# board_ports.net
KiCad netlist of a schematic drawn in Altium Designer
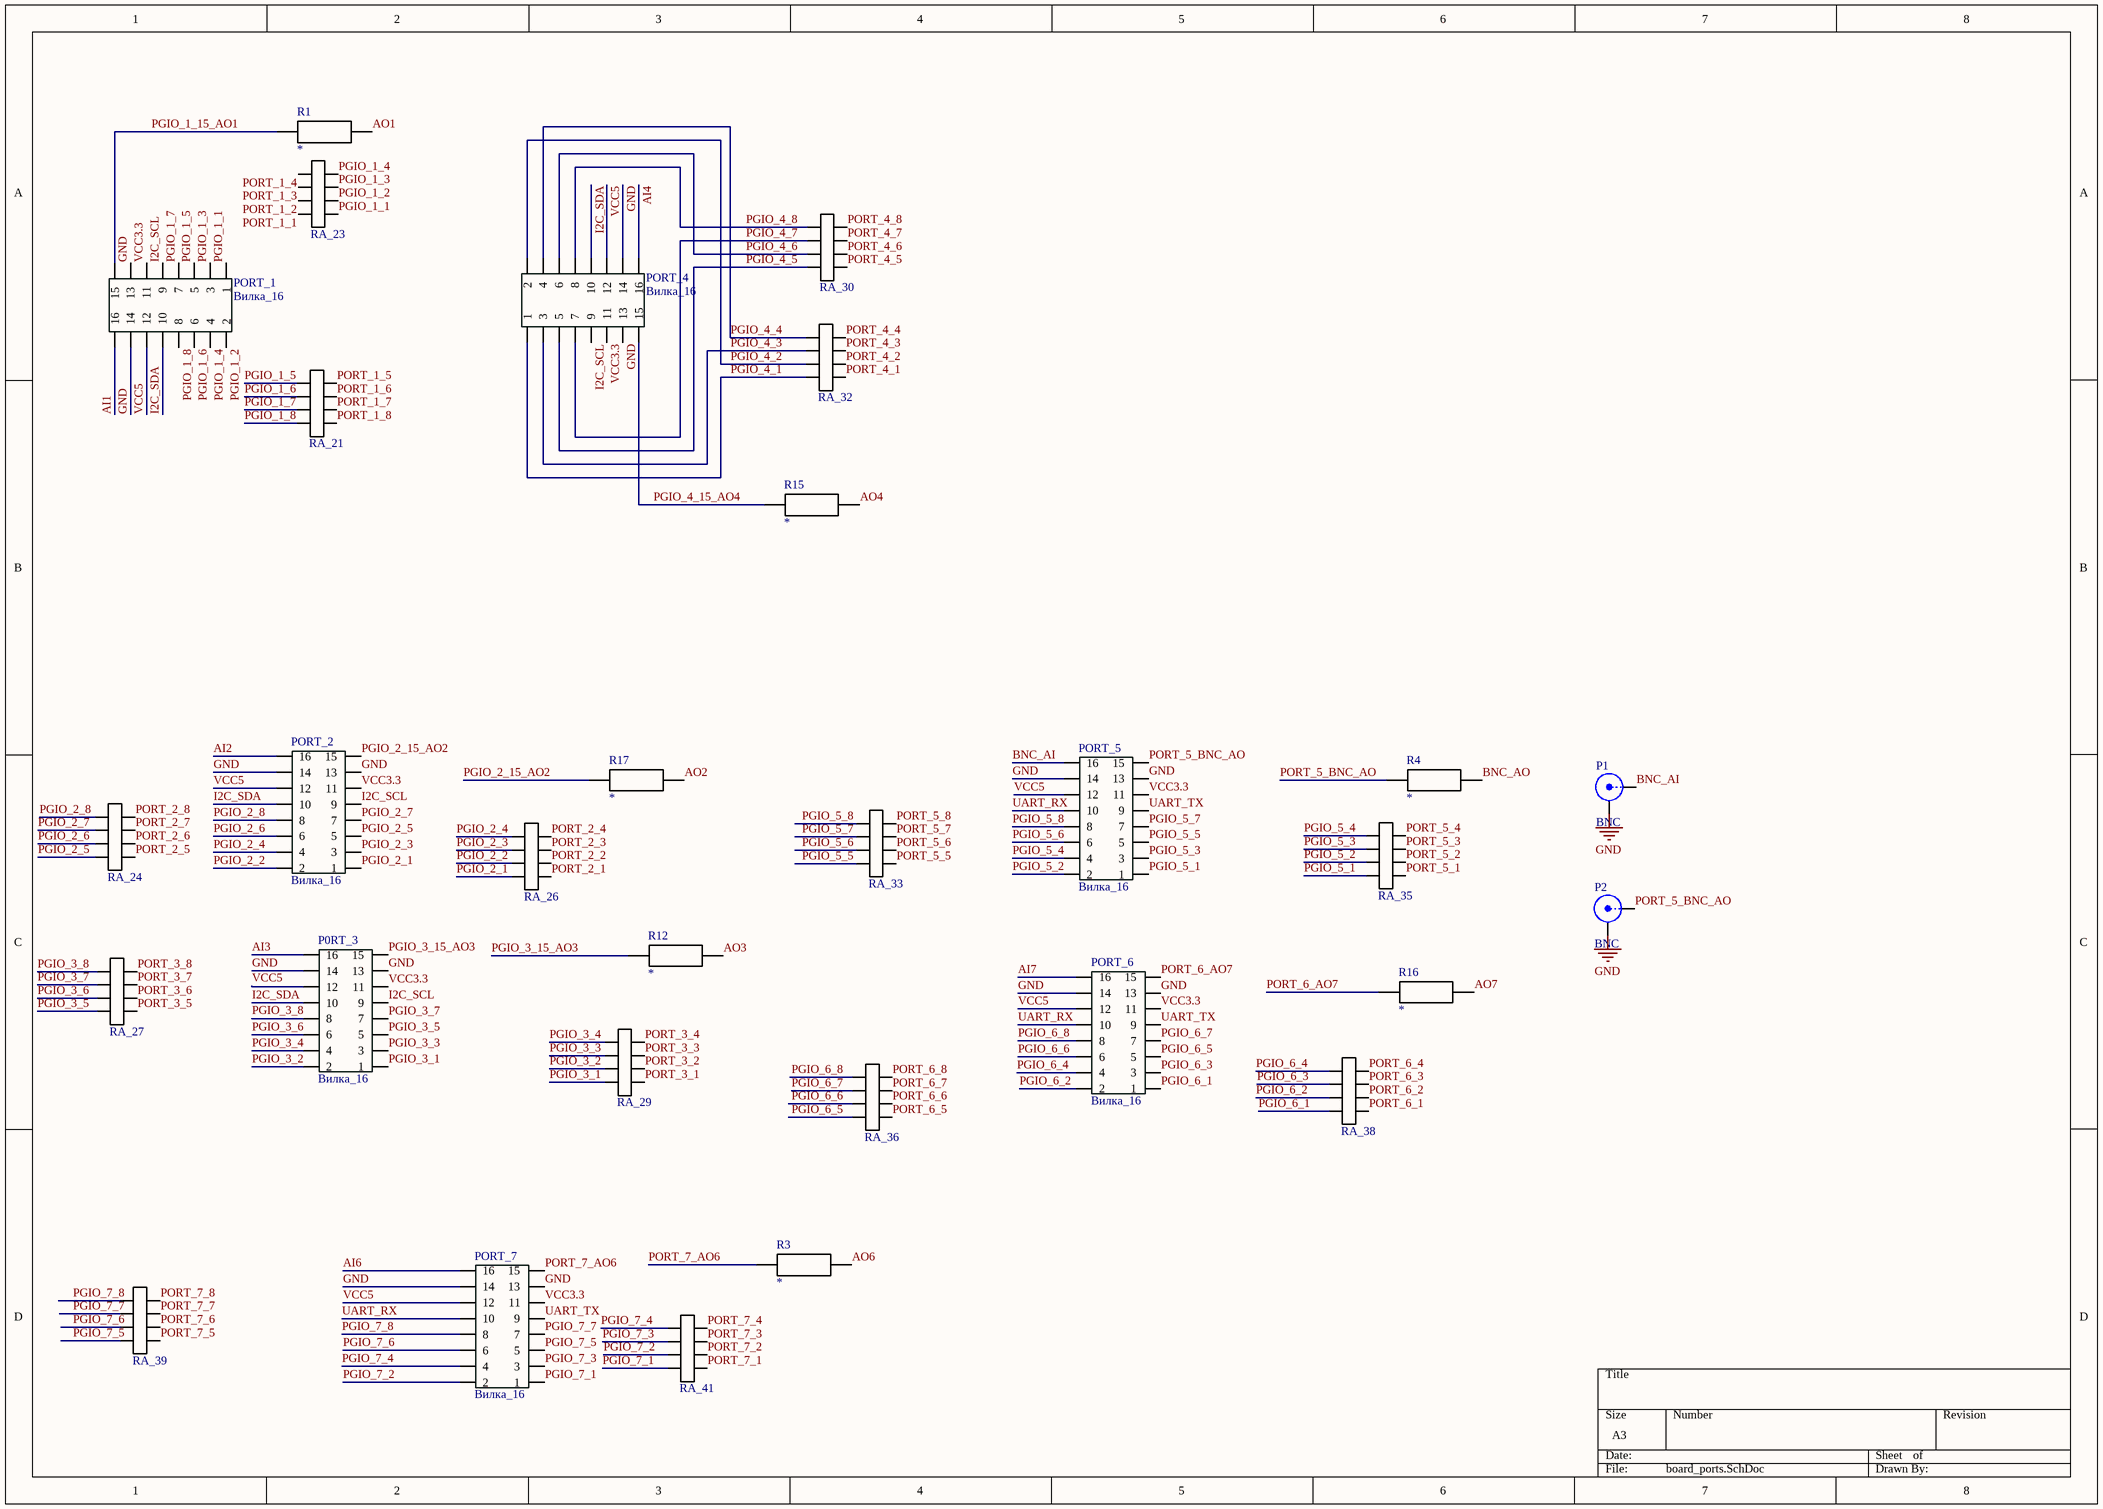
[diagram p0: board_ports.SchDoc]

(export (version "E")
  (design (tool "Eeschema 10.0.6"))
  (components
    (comp (ref "P0RT_3")
      (value "Вилка_16")
      (footprint "elvis_lib:DS1013-16")
      (description "16_pin")
      (libsource (lib "elvis_lib") (part "DS1013-16"))
    )
    (comp (ref "P1")
      (value "BNC")
      (footprint "BNC_RA CON")
      (description "BNC Elbow Connector")
      (fields (field (name "PUBLISHER") "Altium Limited"))
      (libsource (lib "Miscellaneous Connectors") (part "BNC"))
    )
    (comp (ref "P2")
      (value "BNC")
      (footprint "BNC_RA CON")
      (description "BNC Elbow Connector")
      (fields (field (name "PUBLISHER") "Altium Limited"))
      (libsource (lib "Miscellaneous Connectors") (part "BNC"))
    )
    (comp (ref "PORT_1")
      (value "Вилка_16")
      (footprint "elvis_lib:DS1013-16")
      (description "16_pin")
      (libsource (lib "elvis_lib") (part "DS1013-16"))
    )
    (comp (ref "PORT_2")
      (value "Вилка_16")
      (footprint "elvis_lib:DS1013-16")
      (description "16_pin")
      (libsource (lib "elvis_lib") (part "DS1013-16"))
    )
    (comp (ref "PORT_4")
      (value "Вилка_16")
      (footprint "elvis_lib:DS1013-16")
      (description "16_pin")
      (libsource (lib "elvis_lib") (part "DS1013-16"))
    )
    (comp (ref "PORT_5")
      (value "Вилка_16")
      (footprint "elvis_lib:DS1013-16")
      (description "16_pin")
      (libsource (lib "elvis_lib") (part "DS1013-16"))
    )
    (comp (ref "PORT_6")
      (value "Вилка_16")
      (footprint "elvis_lib:DS1013-16")
      (description "16_pin")
      (libsource (lib "elvis_lib") (part "DS1013-16"))
    )
    (comp (ref "PORT_7")
      (value "Вилка_16")
      (footprint "elvis_lib:DS1013-16")
      (description "16_pin")
      (libsource (lib "elvis_lib") (part "DS1013-16"))
    )
    (comp (ref "R1") (value "*") (footprint "elvis_lib:R0805") (libsource (lib "elvis_lib") (part "R0805")))
    (comp (ref "R3") (value "*") (footprint "elvis_lib:R0805") (libsource (lib "elvis_lib") (part "R0805")))
    (comp (ref "R4") (value "*") (footprint "elvis_lib:R0805") (libsource (lib "elvis_lib") (part "R0805")))
    (comp (ref "R12") (value "*") (footprint "elvis_lib:R0805") (libsource (lib "elvis_lib") (part "R0805")))
    (comp (ref "R15") (value "*") (footprint "elvis_lib:R0805") (libsource (lib "elvis_lib") (part "R0805")))
    (comp (ref "R16") (value "*") (footprint "elvis_lib:R0805") (libsource (lib "elvis_lib") (part "R0805")))
    (comp (ref "R17") (value "*") (footprint "elvis_lib:R0805") (libsource (lib "elvis_lib") (part "R0805")))
    (comp (ref "RA_21")
      (value "Bourns CAT16-102J4LF_1")
      (footprint "CAT16-102J4_NEW")
      (libsource (lib "elvis_lib") (part "Bourns CAT16-102J4LF_1"))
    )
    (comp (ref "RA_23")
      (value "Bourns CAT16-102J4LF_1")
      (footprint "CAT16-102J4_NEW")
      (libsource (lib "elvis_lib") (part "Bourns CAT16-102J4LF_1"))
    )
    (comp (ref "RA_24")
      (value "Bourns CAT16-102J4LF_1")
      (footprint "CAT16-102J4_NEW")
      (libsource (lib "elvis_lib") (part "Bourns CAT16-102J4LF_1"))
    )
    (comp (ref "RA_26")
      (value "Bourns CAT16-102J4LF_1")
      (footprint "CAT16-102J4_NEW")
      (libsource (lib "elvis_lib") (part "Bourns CAT16-102J4LF_1"))
    )
    (comp (ref "RA_27")
      (value "Bourns CAT16-102J4LF_1")
      (footprint "CAT16-102J4_NEW")
      (libsource (lib "elvis_lib") (part "Bourns CAT16-102J4LF_1"))
    )
    (comp (ref "RA_29")
      (value "Bourns CAT16-102J4LF_1")
      (footprint "CAT16-102J4_NEW")
      (libsource (lib "elvis_lib") (part "Bourns CAT16-102J4LF_1"))
    )
    (comp (ref "RA_30")
      (value "Bourns CAT16-102J4LF_1")
      (footprint "CAT16-102J4_NEW")
      (libsource (lib "elvis_lib") (part "Bourns CAT16-102J4LF_1"))
    )
    (comp (ref "RA_32")
      (value "Bourns CAT16-102J4LF_1")
      (footprint "CAT16-102J4_NEW")
      (libsource (lib "elvis_lib") (part "Bourns CAT16-102J4LF_1"))
    )
    (comp (ref "RA_33")
      (value "Bourns CAT16-102J4LF_1")
      (footprint "CAT16-102J4_NEW")
      (libsource (lib "elvis_lib") (part "Bourns CAT16-102J4LF_1"))
    )
    (comp (ref "RA_35")
      (value "Bourns CAT16-102J4LF_1")
      (footprint "CAT16-102J4_NEW")
      (libsource (lib "elvis_lib") (part "Bourns CAT16-102J4LF_1"))
    )
    (comp (ref "RA_36")
      (value "Bourns CAT16-102J4LF_1")
      (footprint "CAT16-102J4_NEW")
      (libsource (lib "elvis_lib") (part "Bourns CAT16-102J4LF_1"))
    )
    (comp (ref "RA_38")
      (value "Bourns CAT16-102J4LF_1")
      (footprint "CAT16-102J4_NEW")
      (libsource (lib "elvis_lib") (part "Bourns CAT16-102J4LF_1"))
    )
    (comp (ref "RA_39")
      (value "Bourns CAT16-102J4LF_1")
      (footprint "CAT16-102J4_NEW")
      (libsource (lib "elvis_lib") (part "Bourns CAT16-102J4LF_1"))
    )
    (comp (ref "RA_41")
      (value "Bourns CAT16-102J4LF_1")
      (footprint "CAT16-102J4_NEW")
      (libsource (lib "elvis_lib") (part "Bourns CAT16-102J4LF_1"))
    )
  )
  (nets
    (net (code "1") (name "/AI1") (class "Default")
      (node (ref "PORT_1") (pin "16") (pinfunction "16_16") (pintype "passive"))
    )
    (net (code "2") (name "/AI2") (class "Default")
      (node (ref "PORT_2") (pin "16") (pinfunction "16_16") (pintype "passive"))
    )
    (net (code "3") (name "/AI3") (class "Default")
      (node (ref "P0RT_3") (pin "16") (pinfunction "16_16") (pintype "passive"))
    )
    (net (code "4") (name "/AI4") (class "Default")
      (node (ref "PORT_4") (pin "16") (pinfunction "16_16") (pintype "passive"))
    )
    (net (code "5") (name "/AI6") (class "Default")
      (node (ref "PORT_7") (pin "16") (pinfunction "16_16") (pintype "passive"))
    )
    (net (code "6") (name "/AI7") (class "Default")
      (node (ref "PORT_6") (pin "16") (pinfunction "16_16") (pintype "passive"))
    )
    (net (code "7") (name "/AO1") (class "Default")
      (node (ref "R1") (pin "2") (pinfunction "2_2") (pintype "passive"))
    )
    (net (code "8") (name "/AO2") (class "Default")
      (node (ref "R17") (pin "2") (pinfunction "2_2") (pintype "passive"))
    )
    (net (code "9") (name "/AO3") (class "Default")
      (node (ref "R12") (pin "2") (pinfunction "2_2") (pintype "passive"))
    )
    (net (code "10") (name "/AO4") (class "Default")
      (node (ref "R15") (pin "2") (pinfunction "2_2") (pintype "passive"))
    )
    (net (code "11") (name "/AO6") (class "Default")
      (node (ref "R3") (pin "2") (pinfunction "2_2") (pintype "passive"))
    )
    (net (code "12") (name "/AO7") (class "Default")
      (node (ref "R16") (pin "2") (pinfunction "2_2") (pintype "passive"))
    )
    (net (code "13") (name "/BNC_AI") (class "Default")
      (node (ref "P1") (pin "1") (pinfunction "X_1") (pintype "passive"))
      (node (ref "PORT_5") (pin "16") (pinfunction "16_16") (pintype "passive"))
    )
    (net (code "14") (name "/BNC_AO") (class "Default")
      (node (ref "R4") (pin "2") (pinfunction "2_2") (pintype "passive"))
    )
    (net (code "15") (name "/I2C_SCL") (class "Default")
      (node (ref "P0RT_3") (pin "9") (pinfunction "9_9") (pintype "passive"))
      (node (ref "PORT_1") (pin "9") (pinfunction "9_9") (pintype "passive"))
      (node (ref "PORT_2") (pin "9") (pinfunction "9_9") (pintype "passive"))
      (node (ref "PORT_4") (pin "9") (pinfunction "9_9") (pintype "passive"))
    )
    (net (code "16") (name "/I2C_SDA") (class "Default")
      (node (ref "P0RT_3") (pin "10") (pinfunction "10_10") (pintype "passive"))
      (node (ref "PORT_1") (pin "10") (pinfunction "10_10") (pintype "passive"))
      (node (ref "PORT_2") (pin "10") (pinfunction "10_10") (pintype "passive"))
      (node (ref "PORT_4") (pin "10") (pinfunction "10_10") (pintype "passive"))
    )
    (net (code "17") (name "/PGIO_1_1") (class "Default")
      (node (ref "PORT_1") (pin "1") (pinfunction "1_1") (pintype "passive"))
      (node (ref "RA_23") (pin "7") (pinfunction "7_7") (pintype "passive"))
    )
    (net (code "18") (name "/PGIO_1_2") (class "Default")
      (node (ref "PORT_1") (pin "2") (pinfunction "2_2") (pintype "passive"))
      (node (ref "RA_23") (pin "6") (pinfunction "6_6") (pintype "passive"))
    )
    (net (code "19") (name "/PGIO_1_3") (class "Default")
      (node (ref "PORT_1") (pin "3") (pinfunction "3_3") (pintype "passive"))
      (node (ref "RA_23") (pin "5") (pinfunction "5_5") (pintype "passive"))
    )
    (net (code "20") (name "/PGIO_1_4") (class "Default")
      (node (ref "PORT_1") (pin "4") (pinfunction "4_4") (pintype "passive"))
      (node (ref "RA_23") (pin "4") (pinfunction "4_4") (pintype "passive"))
    )
    (net (code "21") (name "/PGIO_1_5") (class "Default")
      (node (ref "PORT_1") (pin "5") (pinfunction "5_5") (pintype "passive"))
      (node (ref "RA_21") (pin "3") (pinfunction "3_3") (pintype "passive"))
    )
    (net (code "22") (name "/PGIO_1_6") (class "Default")
      (node (ref "PORT_1") (pin "6") (pinfunction "6_6") (pintype "passive"))
      (node (ref "RA_21") (pin "2") (pinfunction "2_2") (pintype "passive"))
    )
    (net (code "23") (name "/PGIO_1_7") (class "Default")
      (node (ref "PORT_1") (pin "7") (pinfunction "7_7") (pintype "passive"))
      (node (ref "RA_21") (pin "1") (pinfunction "1_1") (pintype "passive"))
    )
    (net (code "24") (name "/PGIO_1_8") (class "Default")
      (node (ref "PORT_1") (pin "8") (pinfunction "8_8") (pintype "passive"))
      (node (ref "RA_21") (pin "0") (pinfunction "0_0") (pintype "passive"))
    )
    (net (code "25") (name "/PGIO_1_15_AO1") (class "Default")
      (node (ref "PORT_1") (pin "15") (pinfunction "15_15") (pintype "passive"))
      (node (ref "R1") (pin "1") (pinfunction "1_1") (pintype "passive"))
    )
    (net (code "26") (name "/PGIO_2_1") (class "Default")
      (node (ref "PORT_2") (pin "1") (pinfunction "1_1") (pintype "passive"))
      (node (ref "RA_26") (pin "4") (pinfunction "4_4") (pintype "passive"))
    )
    (net (code "27") (name "/PGIO_2_2") (class "Default")
      (node (ref "PORT_2") (pin "2") (pinfunction "2_2") (pintype "passive"))
      (node (ref "RA_26") (pin "5") (pinfunction "5_5") (pintype "passive"))
    )
    (net (code "28") (name "/PGIO_2_3") (class "Default")
      (node (ref "PORT_2") (pin "3") (pinfunction "3_3") (pintype "passive"))
      (node (ref "RA_26") (pin "6") (pinfunction "6_6") (pintype "passive"))
    )
    (net (code "29") (name "/PGIO_2_4") (class "Default")
      (node (ref "PORT_2") (pin "4") (pinfunction "4_4") (pintype "passive"))
      (node (ref "RA_26") (pin "7") (pinfunction "7_7") (pintype "passive"))
    )
    (net (code "30") (name "/PGIO_2_5") (class "Default")
      (node (ref "PORT_2") (pin "5") (pinfunction "5_5") (pintype "passive"))
      (node (ref "RA_24") (pin "0") (pinfunction "0_0") (pintype "passive"))
    )
    (net (code "31") (name "/PGIO_2_6") (class "Default")
      (node (ref "PORT_2") (pin "6") (pinfunction "6_6") (pintype "passive"))
      (node (ref "RA_24") (pin "1") (pinfunction "1_1") (pintype "passive"))
    )
    (net (code "32") (name "/PGIO_2_7") (class "Default")
      (node (ref "PORT_2") (pin "7") (pinfunction "7_7") (pintype "passive"))
      (node (ref "RA_24") (pin "2") (pinfunction "2_2") (pintype "passive"))
    )
    (net (code "33") (name "/PGIO_2_8") (class "Default")
      (node (ref "PORT_2") (pin "8") (pinfunction "8_8") (pintype "passive"))
      (node (ref "RA_24") (pin "3") (pinfunction "3_3") (pintype "passive"))
    )
    (net (code "34") (name "/PGIO_2_15_AO2") (class "Default")
      (node (ref "PORT_2") (pin "15") (pinfunction "15_15") (pintype "passive"))
      (node (ref "R17") (pin "1") (pinfunction "1_1") (pintype "passive"))
    )
    (net (code "35") (name "/PGIO_3_1") (class "Default")
      (node (ref "P0RT_3") (pin "1") (pinfunction "1_1") (pintype "passive"))
      (node (ref "RA_29") (pin "0") (pinfunction "0_0") (pintype "passive"))
    )
    (net (code "36") (name "/PGIO_3_2") (class "Default")
      (node (ref "P0RT_3") (pin "2") (pinfunction "2_2") (pintype "passive"))
      (node (ref "RA_29") (pin "1") (pinfunction "1_1") (pintype "passive"))
    )
    (net (code "37") (name "/PGIO_3_3") (class "Default")
      (node (ref "P0RT_3") (pin "3") (pinfunction "3_3") (pintype "passive"))
      (node (ref "RA_29") (pin "2") (pinfunction "2_2") (pintype "passive"))
    )
    (net (code "38") (name "/PGIO_3_4") (class "Default")
      (node (ref "P0RT_3") (pin "4") (pinfunction "4_4") (pintype "passive"))
      (node (ref "RA_29") (pin "3") (pinfunction "3_3") (pintype "passive"))
    )
    (net (code "39") (name "/PGIO_3_5") (class "Default")
      (node (ref "P0RT_3") (pin "5") (pinfunction "5_5") (pintype "passive"))
      (node (ref "RA_27") (pin "0") (pinfunction "0_0") (pintype "passive"))
    )
    (net (code "40") (name "/PGIO_3_6") (class "Default")
      (node (ref "P0RT_3") (pin "6") (pinfunction "6_6") (pintype "passive"))
      (node (ref "RA_27") (pin "1") (pinfunction "1_1") (pintype "passive"))
    )
    (net (code "41") (name "/PGIO_3_7") (class "Default")
      (node (ref "P0RT_3") (pin "7") (pinfunction "7_7") (pintype "passive"))
      (node (ref "RA_27") (pin "2") (pinfunction "2_2") (pintype "passive"))
    )
    (net (code "42") (name "/PGIO_3_8") (class "Default")
      (node (ref "P0RT_3") (pin "8") (pinfunction "8_8") (pintype "passive"))
      (node (ref "RA_27") (pin "3") (pinfunction "3_3") (pintype "passive"))
    )
    (net (code "43") (name "/PGIO_3_15_AO3") (class "Default")
      (node (ref "P0RT_3") (pin "15") (pinfunction "15_15") (pintype "passive"))
      (node (ref "R12") (pin "1") (pinfunction "1_1") (pintype "passive"))
    )
    (net (code "44") (name "/PGIO_4_1") (class "Default")
      (node (ref "PORT_4") (pin "1") (pinfunction "1_1") (pintype "passive"))
      (node (ref "RA_32") (pin "4") (pinfunction "4_4") (pintype "passive"))
    )
    (net (code "45") (name "/PGIO_4_2") (class "Default")
      (node (ref "PORT_4") (pin "2") (pinfunction "2_2") (pintype "passive"))
      (node (ref "RA_32") (pin "5") (pinfunction "5_5") (pintype "passive"))
    )
    (net (code "46") (name "/PGIO_4_3") (class "Default")
      (node (ref "PORT_4") (pin "3") (pinfunction "3_3") (pintype "passive"))
      (node (ref "RA_32") (pin "6") (pinfunction "6_6") (pintype "passive"))
    )
    (net (code "47") (name "/PGIO_4_4") (class "Default")
      (node (ref "PORT_4") (pin "4") (pinfunction "4_4") (pintype "passive"))
      (node (ref "RA_32") (pin "7") (pinfunction "7_7") (pintype "passive"))
    )
    (net (code "48") (name "/PGIO_4_5") (class "Default")
      (node (ref "PORT_4") (pin "5") (pinfunction "5_5") (pintype "passive"))
      (node (ref "RA_30") (pin "4") (pinfunction "4_4") (pintype "passive"))
    )
    (net (code "49") (name "/PGIO_4_6") (class "Default")
      (node (ref "PORT_4") (pin "6") (pinfunction "6_6") (pintype "passive"))
      (node (ref "RA_30") (pin "5") (pinfunction "5_5") (pintype "passive"))
    )
    (net (code "50") (name "/PGIO_4_7") (class "Default")
      (node (ref "PORT_4") (pin "7") (pinfunction "7_7") (pintype "passive"))
      (node (ref "RA_30") (pin "6") (pinfunction "6_6") (pintype "passive"))
    )
    (net (code "51") (name "/PGIO_4_8") (class "Default")
      (node (ref "PORT_4") (pin "8") (pinfunction "8_8") (pintype "passive"))
      (node (ref "RA_30") (pin "7") (pinfunction "7_7") (pintype "passive"))
    )
    (net (code "52") (name "/PGIO_4_15_AO4") (class "Default")
      (node (ref "PORT_4") (pin "15") (pinfunction "15_15") (pintype "passive"))
      (node (ref "R15") (pin "1") (pinfunction "1_1") (pintype "passive"))
    )
    (net (code "53") (name "/PGIO_5_1") (class "Default")
      (node (ref "PORT_5") (pin "1") (pinfunction "1_1") (pintype "passive"))
      (node (ref "RA_35") (pin "0") (pinfunction "0_0") (pintype "passive"))
    )
    (net (code "54") (name "/PGIO_5_2") (class "Default")
      (node (ref "PORT_5") (pin "2") (pinfunction "2_2") (pintype "passive"))
      (node (ref "RA_35") (pin "1") (pinfunction "1_1") (pintype "passive"))
    )
    (net (code "55") (name "/PGIO_5_3") (class "Default")
      (node (ref "PORT_5") (pin "3") (pinfunction "3_3") (pintype "passive"))
      (node (ref "RA_35") (pin "2") (pinfunction "2_2") (pintype "passive"))
    )
    (net (code "56") (name "/PGIO_5_4") (class "Default")
      (node (ref "PORT_5") (pin "4") (pinfunction "4_4") (pintype "passive"))
      (node (ref "RA_35") (pin "3") (pinfunction "3_3") (pintype "passive"))
    )
    (net (code "57") (name "/PGIO_5_5") (class "Default")
      (node (ref "PORT_5") (pin "5") (pinfunction "5_5") (pintype "passive"))
      (node (ref "RA_33") (pin "0") (pinfunction "0_0") (pintype "passive"))
    )
    (net (code "58") (name "/PGIO_5_6") (class "Default")
      (node (ref "PORT_5") (pin "6") (pinfunction "6_6") (pintype "passive"))
      (node (ref "RA_33") (pin "1") (pinfunction "1_1") (pintype "passive"))
    )
    (net (code "59") (name "/PGIO_5_7") (class "Default")
      (node (ref "PORT_5") (pin "7") (pinfunction "7_7") (pintype "passive"))
      (node (ref "RA_33") (pin "2") (pinfunction "2_2") (pintype "passive"))
    )
    (net (code "60") (name "/PGIO_5_8") (class "Default")
      (node (ref "PORT_5") (pin "8") (pinfunction "8_8") (pintype "passive"))
      (node (ref "RA_33") (pin "3") (pinfunction "3_3") (pintype "passive"))
    )
    (net (code "61") (name "/PGIO_6_1") (class "Default")
      (node (ref "PORT_6") (pin "1") (pinfunction "1_1") (pintype "passive"))
      (node (ref "RA_38") (pin "4") (pinfunction "4_4") (pintype "passive"))
    )
    (net (code "62") (name "/PGIO_6_2") (class "Default")
      (node (ref "PORT_6") (pin "2") (pinfunction "2_2") (pintype "passive"))
      (node (ref "RA_38") (pin "5") (pinfunction "5_5") (pintype "passive"))
    )
    (net (code "63") (name "/PGIO_6_3") (class "Default")
      (node (ref "PORT_6") (pin "3") (pinfunction "3_3") (pintype "passive"))
      (node (ref "RA_38") (pin "6") (pinfunction "6_6") (pintype "passive"))
    )
    (net (code "64") (name "/PGIO_6_4") (class "Default")
      (node (ref "PORT_6") (pin "4") (pinfunction "4_4") (pintype "passive"))
      (node (ref "RA_38") (pin "7") (pinfunction "7_7") (pintype "passive"))
    )
    (net (code "65") (name "/PGIO_6_5") (class "Default")
      (node (ref "PORT_6") (pin "5") (pinfunction "5_5") (pintype "passive"))
      (node (ref "RA_36") (pin "0") (pinfunction "0_0") (pintype "passive"))
    )
    (net (code "66") (name "/PGIO_6_6") (class "Default")
      (node (ref "PORT_6") (pin "6") (pinfunction "6_6") (pintype "passive"))
      (node (ref "RA_36") (pin "1") (pinfunction "1_1") (pintype "passive"))
    )
    (net (code "67") (name "/PGIO_6_7") (class "Default")
      (node (ref "PORT_6") (pin "7") (pinfunction "7_7") (pintype "passive"))
      (node (ref "RA_36") (pin "2") (pinfunction "2_2") (pintype "passive"))
    )
    (net (code "68") (name "/PGIO_6_8") (class "Default")
      (node (ref "PORT_6") (pin "8") (pinfunction "8_8") (pintype "passive"))
      (node (ref "RA_36") (pin "3") (pinfunction "3_3") (pintype "passive"))
    )
    (net (code "69") (name "/PGIO_7_1") (class "Default")
      (node (ref "PORT_7") (pin "1") (pinfunction "1_1") (pintype "passive"))
      (node (ref "RA_41") (pin "4") (pinfunction "4_4") (pintype "passive"))
    )
    (net (code "70") (name "/PGIO_7_2") (class "Default")
      (node (ref "PORT_7") (pin "2") (pinfunction "2_2") (pintype "passive"))
      (node (ref "RA_41") (pin "5") (pinfunction "5_5") (pintype "passive"))
    )
    (net (code "71") (name "/PGIO_7_3") (class "Default")
      (node (ref "PORT_7") (pin "3") (pinfunction "3_3") (pintype "passive"))
      (node (ref "RA_41") (pin "6") (pinfunction "6_6") (pintype "passive"))
    )
    (net (code "72") (name "/PGIO_7_4") (class "Default")
      (node (ref "PORT_7") (pin "4") (pinfunction "4_4") (pintype "passive"))
      (node (ref "RA_41") (pin "7") (pinfunction "7_7") (pintype "passive"))
    )
    (net (code "73") (name "/PGIO_7_5") (class "Default")
      (node (ref "PORT_7") (pin "5") (pinfunction "5_5") (pintype "passive"))
      (node (ref "RA_39") (pin "0") (pinfunction "0_0") (pintype "passive"))
    )
    (net (code "74") (name "/PGIO_7_6") (class "Default")
      (node (ref "PORT_7") (pin "6") (pinfunction "6_6") (pintype "passive"))
      (node (ref "RA_39") (pin "1") (pinfunction "1_1") (pintype "passive"))
    )
    (net (code "75") (name "/PGIO_7_7") (class "Default")
      (node (ref "PORT_7") (pin "7") (pinfunction "7_7") (pintype "passive"))
      (node (ref "RA_39") (pin "2") (pinfunction "2_2") (pintype "passive"))
    )
    (net (code "76") (name "/PGIO_7_8") (class "Default")
      (node (ref "PORT_7") (pin "8") (pinfunction "8_8") (pintype "passive"))
      (node (ref "RA_39") (pin "3") (pinfunction "3_3") (pintype "passive"))
    )
    (net (code "77") (name "/PORT_1_1") (class "Default")
      (node (ref "RA_23") (pin "0") (pinfunction "0_0") (pintype "passive"))
    )
    (net (code "78") (name "/PORT_1_2") (class "Default")
      (node (ref "RA_23") (pin "1") (pinfunction "1_1") (pintype "passive"))
    )
    (net (code "79") (name "/PORT_1_3") (class "Default")
      (node (ref "RA_23") (pin "2") (pinfunction "2_2") (pintype "passive"))
    )
    (net (code "80") (name "/PORT_1_4") (class "Default")
      (node (ref "RA_23") (pin "3") (pinfunction "3_3") (pintype "passive"))
    )
    (net (code "81") (name "/PORT_1_5") (class "Default")
      (node (ref "RA_21") (pin "4") (pinfunction "4_4") (pintype "passive"))
    )
    (net (code "82") (name "/PORT_1_6") (class "Default")
      (node (ref "RA_21") (pin "5") (pinfunction "5_5") (pintype "passive"))
    )
    (net (code "83") (name "/PORT_1_7") (class "Default")
      (node (ref "RA_21") (pin "6") (pinfunction "6_6") (pintype "passive"))
    )
    (net (code "84") (name "/PORT_1_8") (class "Default")
      (node (ref "RA_21") (pin "7") (pinfunction "7_7") (pintype "passive"))
    )
    (net (code "85") (name "/PORT_2_1") (class "Default")
      (node (ref "RA_26") (pin "3") (pinfunction "3_3") (pintype "passive"))
    )
    (net (code "86") (name "/PORT_2_2") (class "Default")
      (node (ref "RA_26") (pin "2") (pinfunction "2_2") (pintype "passive"))
    )
    (net (code "87") (name "/PORT_2_3") (class "Default")
      (node (ref "RA_26") (pin "1") (pinfunction "1_1") (pintype "passive"))
    )
    (net (code "88") (name "/PORT_2_4") (class "Default")
      (node (ref "RA_26") (pin "0") (pinfunction "0_0") (pintype "passive"))
    )
    (net (code "89") (name "/PORT_2_5") (class "Default")
      (node (ref "RA_24") (pin "7") (pinfunction "7_7") (pintype "passive"))
    )
    (net (code "90") (name "/PORT_2_6") (class "Default")
      (node (ref "RA_24") (pin "6") (pinfunction "6_6") (pintype "passive"))
    )
    (net (code "91") (name "/PORT_2_7") (class "Default")
      (node (ref "RA_24") (pin "5") (pinfunction "5_5") (pintype "passive"))
    )
    (net (code "92") (name "/PORT_2_8") (class "Default")
      (node (ref "RA_24") (pin "4") (pinfunction "4_4") (pintype "passive"))
    )
    (net (code "93") (name "/PORT_3_1") (class "Default")
      (node (ref "RA_29") (pin "7") (pinfunction "7_7") (pintype "passive"))
    )
    (net (code "94") (name "/PORT_3_2") (class "Default")
      (node (ref "RA_29") (pin "6") (pinfunction "6_6") (pintype "passive"))
    )
    (net (code "95") (name "/PORT_3_3") (class "Default")
      (node (ref "RA_29") (pin "5") (pinfunction "5_5") (pintype "passive"))
    )
    (net (code "96") (name "/PORT_3_4") (class "Default")
      (node (ref "RA_29") (pin "4") (pinfunction "4_4") (pintype "passive"))
    )
    (net (code "97") (name "/PORT_3_5") (class "Default")
      (node (ref "RA_27") (pin "7") (pinfunction "7_7") (pintype "passive"))
    )
    (net (code "98") (name "/PORT_3_6") (class "Default")
      (node (ref "RA_27") (pin "6") (pinfunction "6_6") (pintype "passive"))
    )
    (net (code "99") (name "/PORT_3_7") (class "Default")
      (node (ref "RA_27") (pin "5") (pinfunction "5_5") (pintype "passive"))
    )
    (net (code "100") (name "/PORT_3_8") (class "Default")
      (node (ref "RA_27") (pin "4") (pinfunction "4_4") (pintype "passive"))
    )
    (net (code "101") (name "/PORT_4_1") (class "Default")
      (node (ref "RA_32") (pin "3") (pinfunction "3_3") (pintype "passive"))
    )
    (net (code "102") (name "/PORT_4_2") (class "Default")
      (node (ref "RA_32") (pin "2") (pinfunction "2_2") (pintype "passive"))
    )
    (net (code "103") (name "/PORT_4_3") (class "Default")
      (node (ref "RA_32") (pin "1") (pinfunction "1_1") (pintype "passive"))
    )
    (net (code "104") (name "/PORT_4_4") (class "Default")
      (node (ref "RA_32") (pin "0") (pinfunction "0_0") (pintype "passive"))
    )
    (net (code "105") (name "/PORT_4_5") (class "Default")
      (node (ref "RA_30") (pin "3") (pinfunction "3_3") (pintype "passive"))
    )
    (net (code "106") (name "/PORT_4_6") (class "Default")
      (node (ref "RA_30") (pin "2") (pinfunction "2_2") (pintype "passive"))
    )
    (net (code "107") (name "/PORT_4_7") (class "Default")
      (node (ref "RA_30") (pin "1") (pinfunction "1_1") (pintype "passive"))
    )
    (net (code "108") (name "/PORT_4_8") (class "Default")
      (node (ref "RA_30") (pin "0") (pinfunction "0_0") (pintype "passive"))
    )
    (net (code "109") (name "/PORT_5_1") (class "Default")
      (node (ref "RA_35") (pin "7") (pinfunction "7_7") (pintype "passive"))
    )
    (net (code "110") (name "/PORT_5_2") (class "Default")
      (node (ref "RA_35") (pin "6") (pinfunction "6_6") (pintype "passive"))
    )
    (net (code "111") (name "/PORT_5_3") (class "Default")
      (node (ref "RA_35") (pin "5") (pinfunction "5_5") (pintype "passive"))
    )
    (net (code "112") (name "/PORT_5_4") (class "Default")
      (node (ref "RA_35") (pin "4") (pinfunction "4_4") (pintype "passive"))
    )
    (net (code "113") (name "/PORT_5_5") (class "Default")
      (node (ref "RA_33") (pin "7") (pinfunction "7_7") (pintype "passive"))
    )
    (net (code "114") (name "/PORT_5_6") (class "Default")
      (node (ref "RA_33") (pin "6") (pinfunction "6_6") (pintype "passive"))
    )
    (net (code "115") (name "/PORT_5_7") (class "Default")
      (node (ref "RA_33") (pin "5") (pinfunction "5_5") (pintype "passive"))
    )
    (net (code "116") (name "/PORT_5_8") (class "Default")
      (node (ref "RA_33") (pin "4") (pinfunction "4_4") (pintype "passive"))
    )
    (net (code "117") (name "/PORT_5_BNC_AO") (class "Default")
      (node (ref "P2") (pin "1") (pinfunction "X_1") (pintype "passive"))
      (node (ref "PORT_5") (pin "15") (pinfunction "15_15") (pintype "passive"))
      (node (ref "R4") (pin "1") (pinfunction "1_1") (pintype "passive"))
    )
    (net (code "118") (name "/PORT_6_1") (class "Default")
      (node (ref "RA_38") (pin "3") (pinfunction "3_3") (pintype "passive"))
    )
    (net (code "119") (name "/PORT_6_2") (class "Default")
      (node (ref "RA_38") (pin "2") (pinfunction "2_2") (pintype "passive"))
    )
    (net (code "120") (name "/PORT_6_3") (class "Default")
      (node (ref "RA_38") (pin "1") (pinfunction "1_1") (pintype "passive"))
    )
    (net (code "121") (name "/PORT_6_4") (class "Default")
      (node (ref "RA_38") (pin "0") (pinfunction "0_0") (pintype "passive"))
    )
    (net (code "122") (name "/PORT_6_5") (class "Default")
      (node (ref "RA_36") (pin "7") (pinfunction "7_7") (pintype "passive"))
    )
    (net (code "123") (name "/PORT_6_6") (class "Default")
      (node (ref "RA_36") (pin "6") (pinfunction "6_6") (pintype "passive"))
    )
    (net (code "124") (name "/PORT_6_7") (class "Default")
      (node (ref "RA_36") (pin "5") (pinfunction "5_5") (pintype "passive"))
    )
    (net (code "125") (name "/PORT_6_8") (class "Default")
      (node (ref "RA_36") (pin "4") (pinfunction "4_4") (pintype "passive"))
    )
    (net (code "126") (name "/PORT_6_AO7") (class "Default")
      (node (ref "PORT_6") (pin "15") (pinfunction "15_15") (pintype "passive"))
      (node (ref "R16") (pin "1") (pinfunction "1_1") (pintype "passive"))
    )
    (net (code "127") (name "/PORT_7_1") (class "Default")
      (node (ref "RA_41") (pin "3") (pinfunction "3_3") (pintype "passive"))
    )
    (net (code "128") (name "/PORT_7_2") (class "Default")
      (node (ref "RA_41") (pin "2") (pinfunction "2_2") (pintype "passive"))
    )
    (net (code "129") (name "/PORT_7_3") (class "Default")
      (node (ref "RA_41") (pin "1") (pinfunction "1_1") (pintype "passive"))
    )
    (net (code "130") (name "/PORT_7_4") (class "Default")
      (node (ref "RA_41") (pin "0") (pinfunction "0_0") (pintype "passive"))
    )
    (net (code "131") (name "/PORT_7_5") (class "Default")
      (node (ref "RA_39") (pin "7") (pinfunction "7_7") (pintype "passive"))
    )
    (net (code "132") (name "/PORT_7_6") (class "Default")
      (node (ref "RA_39") (pin "6") (pinfunction "6_6") (pintype "passive"))
    )
    (net (code "133") (name "/PORT_7_7") (class "Default")
      (node (ref "RA_39") (pin "5") (pinfunction "5_5") (pintype "passive"))
    )
    (net (code "134") (name "/PORT_7_8") (class "Default")
      (node (ref "RA_39") (pin "4") (pinfunction "4_4") (pintype "passive"))
    )
    (net (code "135") (name "/PORT_7_AO6") (class "Default")
      (node (ref "PORT_7") (pin "15") (pinfunction "15_15") (pintype "passive"))
      (node (ref "R3") (pin "1") (pinfunction "1_1") (pintype "passive"))
    )
    (net (code "136") (name "/UART_RX") (class "Default")
      (node (ref "PORT_5") (pin "10") (pinfunction "10_10") (pintype "passive"))
      (node (ref "PORT_6") (pin "10") (pinfunction "10_10") (pintype "passive"))
      (node (ref "PORT_7") (pin "10") (pinfunction "10_10") (pintype "passive"))
    )
    (net (code "137") (name "/UART_TX") (class "Default")
      (node (ref "PORT_5") (pin "9") (pinfunction "9_9") (pintype "passive"))
      (node (ref "PORT_6") (pin "9") (pinfunction "9_9") (pintype "passive"))
      (node (ref "PORT_7") (pin "9") (pinfunction "9_9") (pintype "passive"))
    )
    (net (code "138") (name "/VCC3.3") (class "Default")
      (node (ref "P0RT_3") (pin "11") (pinfunction "11_11") (pintype "passive"))
      (node (ref "PORT_1") (pin "11") (pinfunction "11_11") (pintype "passive"))
      (node (ref "PORT_2") (pin "11") (pinfunction "11_11") (pintype "passive"))
      (node (ref "PORT_4") (pin "11") (pinfunction "11_11") (pintype "passive"))
      (node (ref "PORT_5") (pin "11") (pinfunction "11_11") (pintype "passive"))
      (node (ref "PORT_6") (pin "11") (pinfunction "11_11") (pintype "passive"))
      (node (ref "PORT_7") (pin "11") (pinfunction "11_11") (pintype "passive"))
    )
    (net (code "139") (name "/VCC5") (class "Default")
      (node (ref "P0RT_3") (pin "12") (pinfunction "12_12") (pintype "passive"))
      (node (ref "PORT_1") (pin "12") (pinfunction "12_12") (pintype "passive"))
      (node (ref "PORT_2") (pin "12") (pinfunction "12_12") (pintype "passive"))
      (node (ref "PORT_4") (pin "12") (pinfunction "12_12") (pintype "passive"))
      (node (ref "PORT_5") (pin "12") (pinfunction "12_12") (pintype "passive"))
      (node (ref "PORT_6") (pin "12") (pinfunction "12_12") (pintype "passive"))
      (node (ref "PORT_7") (pin "12") (pinfunction "12_12") (pintype "passive"))
    )
    (net (code "140") (name "GND") (class "Default")
      (node (ref "P0RT_3") (pin "13") (pinfunction "13_13") (pintype "passive"))
      (node (ref "P0RT_3") (pin "14") (pinfunction "14_14") (pintype "passive"))
      (node (ref "P1") (pin "2") (pinfunction "Y_2") (pintype "passive"))
      (node (ref "P2") (pin "2") (pinfunction "Y_2") (pintype "passive"))
      (node (ref "PORT_1") (pin "13") (pinfunction "13_13") (pintype "passive"))
      (node (ref "PORT_1") (pin "14") (pinfunction "14_14") (pintype "passive"))
      (node (ref "PORT_2") (pin "13") (pinfunction "13_13") (pintype "passive"))
      (node (ref "PORT_2") (pin "14") (pinfunction "14_14") (pintype "passive"))
      (node (ref "PORT_4") (pin "13") (pinfunction "13_13") (pintype "passive"))
      (node (ref "PORT_4") (pin "14") (pinfunction "14_14") (pintype "passive"))
      (node (ref "PORT_5") (pin "13") (pinfunction "13_13") (pintype "passive"))
      (node (ref "PORT_5") (pin "14") (pinfunction "14_14") (pintype "passive"))
      (node (ref "PORT_6") (pin "13") (pinfunction "13_13") (pintype "passive"))
      (node (ref "PORT_6") (pin "14") (pinfunction "14_14") (pintype "passive"))
      (node (ref "PORT_7") (pin "13") (pinfunction "13_13") (pintype "passive"))
      (node (ref "PORT_7") (pin "14") (pinfunction "14_14") (pintype "passive"))
    )
  )
)
